# MCU.net
KiCad netlist of a schematic drawn in Altium Designer
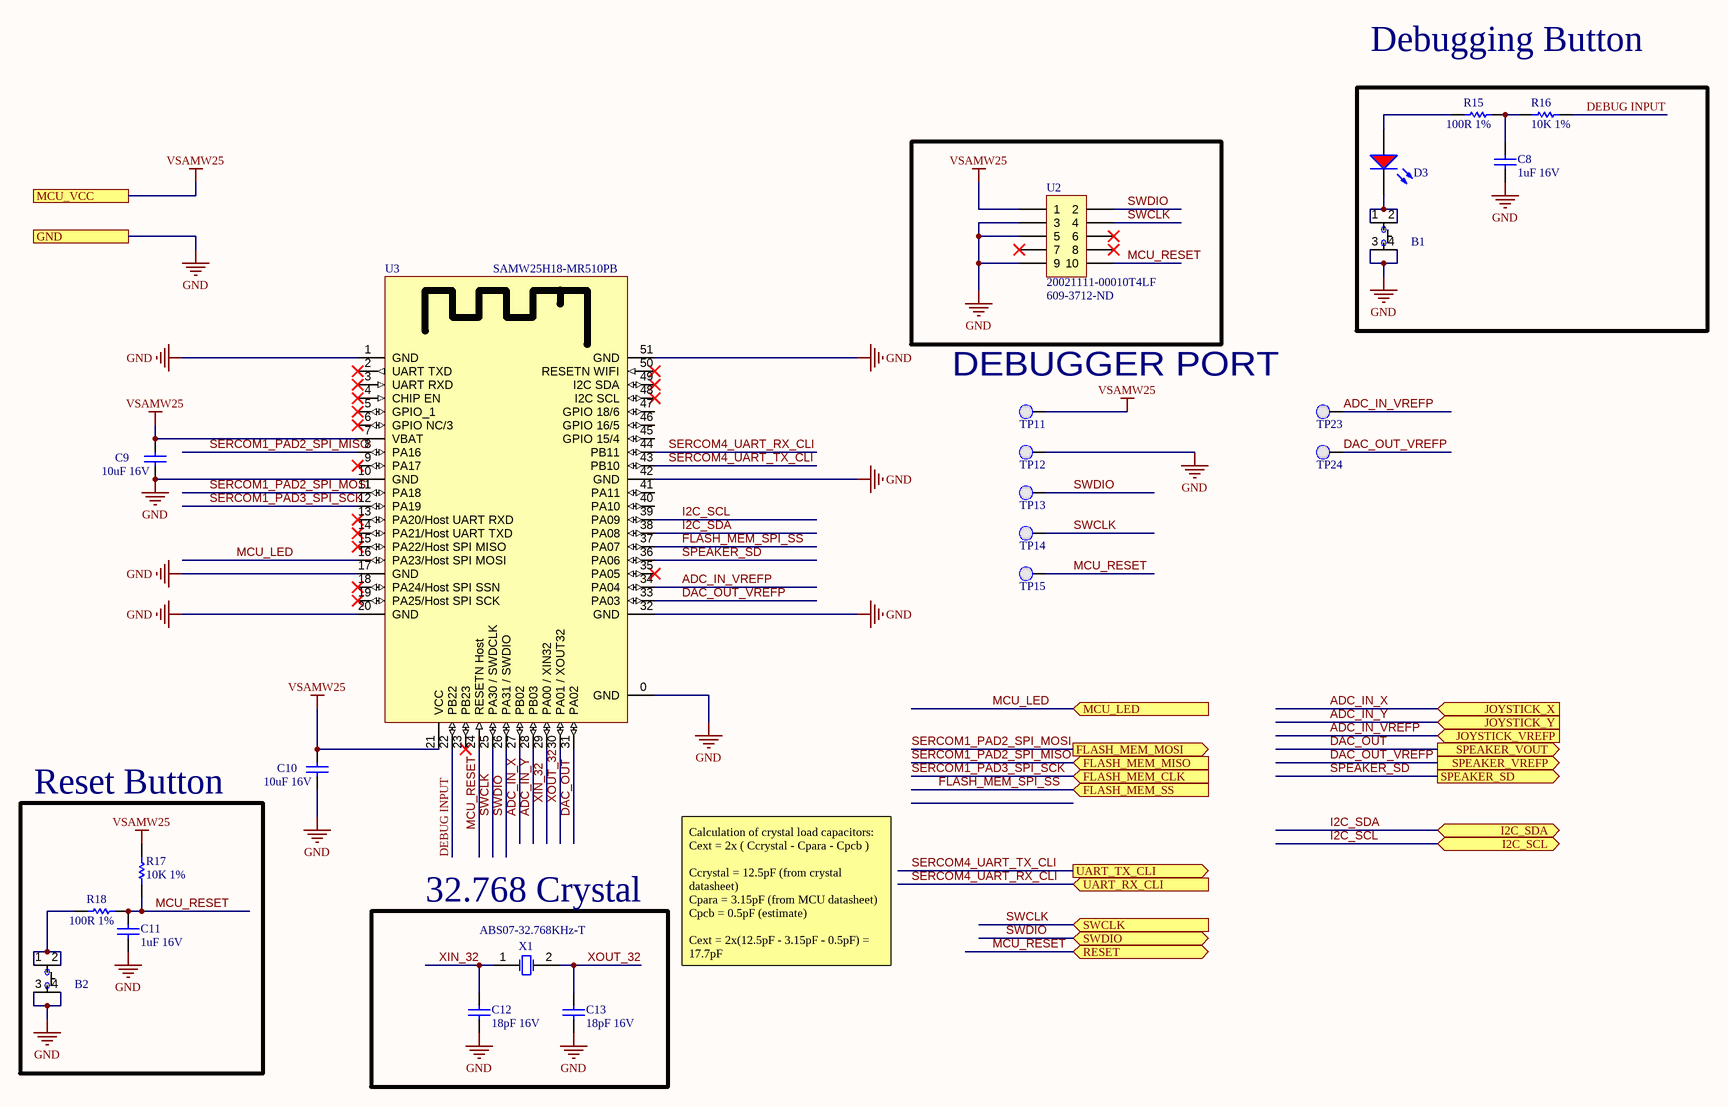
[diagram p0: MCU.SchDoc]

(export (version "E")
  (design (tool "Eeschema 10.0.6"))
  (components
    (comp (ref "B1")
      (value "PTS810 SJK 250 SMTR LFS")
      (footprint "PTS810 SJK 250 SMTR LFS")
      (description "SWITCH TACTILE SPST-NO 0.05A 16V Tactile Switch SPST-NO Top Actuated Surface Mount")
      (fields
        (field (name "MANUFACTURER") "ITT /  C&K Components")
        (field (name "MANUFACTURER PART NUMBER") "PTS810SJK250SMTRLFS")
      )
      (libsource (lib "Schematics") (part "PTS810 SJK 250 SMTR LFS"))
    )
    (comp (ref "B2")
      (value "PTS810 SJK 250 SMTR LFS")
      (footprint "PTS810 SJK 250 SMTR LFS")
      (description "SWITCH TACTILE SPST-NO 0.05A 16V Tactile Switch SPST-NO Top Actuated Surface Mount")
      (fields
        (field (name "MANUFACTURER") "ITT /  C&K Components")
        (field (name "MANUFACTURER PART NUMBER") "PTS810SJK250SMTRLFS")
      )
      (libsource (lib "Schematics") (part "PTS810 SJK 250 SMTR LFS"))
    )
    (comp (ref "C8")
      (value "1uF 16V")
      (footprint "CAPC0603(1608)100_N")
      (description "CAP 1uF 16V ±5% 0603 (1608 Metric) Thickness 1mm SMD")
      (fields (field (name "TOLERANCE") "Â±5%"))
      (libsource (lib "Altium Content Vault") (part "CAP"))
    )
    (comp (ref "C9")
      (value "10uF 16V")
      (footprint "CAPC0805(2012)145_L")
      (description "CAP 10uF 16V ±10% 0805 (2012 Metric) Thickness 1.45mm SMD")
      (fields (field (name "TOLERANCE") "Â±10%"))
      (libsource (lib "Altium Content Vault") (part "CAP"))
    )
    (comp (ref "C10")
      (value "10uF 16V")
      (footprint "CAPC0805(2012)145_L")
      (description "CAP 10uF 16V ±10% 0805 (2012 Metric) Thickness 1.45mm SMD")
      (fields (field (name "TOLERANCE") "Â±10%"))
      (libsource (lib "Altium Content Vault") (part "CAP"))
    )
    (comp (ref "C11")
      (value "1uF 16V")
      (footprint "CAPC0603(1608)100_N")
      (description "CAP 1uF 16V ±5% 0603 (1608 Metric) Thickness 1mm SMD")
      (fields (field (name "TOLERANCE") "Â±5%"))
      (libsource (lib "Altium Content Vault") (part "CAP"))
    )
    (comp (ref "C12")
      (value "18pF 16V")
      (footprint "CAPC0603(1608)100_N")
      (description "CAP 18pF 16V ±5% 0603 (1608 Metric) Thickness 1mm SMD")
      (fields (field (name "TOLERANCE") "Â±5%"))
      (libsource (lib "Altium Content Vault") (part "CAP"))
    )
    (comp (ref "C13")
      (value "18pF 16V")
      (footprint "CAPC0603(1608)100_N")
      (description "CAP 18pF 16V ±5% 0603 (1608 Metric) Thickness 1mm SMD")
      (fields (field (name "TOLERANCE") "Â±5%"))
      (libsource (lib "Altium Content Vault") (part "CAP"))
    )
    (comp (ref "D3")
      (value "LTST-C170CKT")
      (footprint "LTST-C170CKT_V")
      (description "LED Uni-Color Red, 100 mW, 200 mA, -55 to 85 degC, 2-Pin SMD, RoHS, Tape and Reel")
      (fields (field (name "MANUFACTURER") "Lite-On"))
      (libsource (lib "Altium Content Vault") (part "LED-RED-AK-2"))
    )
    (comp (ref "R15")
      (value "100R 1%")
      (footprint "RESC0603(1608)_N")
      (description "100R 0.1W 1% 0603 (1608 Metric)  SMD")
      (fields (field (name "TOLERANCE") "1 %") (field (name "POWER") "0.1 W"))
      (libsource (lib "Altium Content Vault") (part "RES"))
    )
    (comp (ref "R16")
      (value "10K 1%")
      (footprint "RESC0603(1608)_N")
      (description "10K 0.1W 1% 0603 (1608 Metric)  SMD")
      (fields (field (name "POWER") "0.1 W") (field (name "TOLERANCE") "1 %"))
      (libsource (lib "Altium Content Vault") (part "RES"))
    )
    (comp (ref "R17")
      (value "10K 1%")
      (footprint "RESC0603(1608)_N")
      (description "10K 0.1W 1% 0603 (1608 Metric)  SMD")
      (fields (field (name "POWER") "0.1 W") (field (name "TOLERANCE") "1 %"))
      (libsource (lib "Altium Content Vault") (part "RES"))
    )
    (comp (ref "R18")
      (value "100R 1%")
      (footprint "RESC0603(1608)_N")
      (description "100R 0.1W 1% 0603 (1608 Metric)  SMD")
      (fields (field (name "TOLERANCE") "1 %") (field (name "POWER") "0.1 W"))
      (libsource (lib "Altium Content Vault") (part "RES"))
    )
    (comp (ref "TP11")
      (value "0.1\" Pad")
      (footprint "PCBComponent")
      (libsource (lib "Components - 12.02.20 - 18.05") (part "0.1{dblquote} Pad-A.4"))
    )
    (comp (ref "TP12")
      (value "0.1\" Pad")
      (footprint "PCBComponent")
      (libsource (lib "Components - 12.02.20 - 18.05") (part "0.1{dblquote} Pad-A.4"))
    )
    (comp (ref "TP13")
      (value "0.1\" Pad")
      (footprint "PCBComponent")
      (libsource (lib "Components - 12.02.20 - 18.05") (part "0.1{dblquote} Pad-A.4"))
    )
    (comp (ref "TP14")
      (value "0.1\" Pad")
      (footprint "PCBComponent")
      (libsource (lib "Components - 12.02.20 - 18.05") (part "0.1{dblquote} Pad-A.4"))
    )
    (comp (ref "TP15")
      (value "0.1\" Pad")
      (footprint "PCBComponent")
      (libsource (lib "Components - 12.02.20 - 18.05") (part "0.1{dblquote} Pad-A.4"))
    )
    (comp (ref "TP23")
      (value "0.1\" Pad")
      (footprint "PCBComponent")
      (libsource (lib "Components - 12.02.20 - 18.05") (part "0.1{dblquote} Pad-A.4"))
    )
    (comp (ref "TP24")
      (value "0.1\" Pad")
      (footprint "PCBComponent")
      (libsource (lib "Components - 12.02.20 - 18.05") (part "0.1{dblquote} Pad-A.4"))
    )
    (comp (ref "U2")
      (value "20021111-00010T4LF")
      (footprint "20021111-00010T4LF")
      (description "CONN HEADER 10POS UNSHD VERT T/H")
      (fields
        (field (name "MANUFACTURER") "Amphenol / FCI")
        (field (name "SUPPLIER PART NUMBER 1") "609-3712-ND")
      )
      (libsource (lib "Schematics") (part "20021111-00010T4LF"))
    )
    (comp (ref "U3")
      (value "SAMW25H18-MR510PB")
      (footprint "SAMW25H18-MR510PB")
      (description "RF TXRX MODULE WIFI TRACE ANT")
      (fields
        (field (name "MANUFACTURER") "Atmel")
        (field (name "MANUFACTURER PART NUMBER") "ATSAMW25H18-MR510PB")
      )
      (libsource (lib "Schematics") (part "SAMW25H18-MR510PB"))
    )
    (comp (ref "X1")
      (value "ABS07-32.768KHz-T")
      (footprint "ABRA-ABS07-2_V")
      (description "Crystal, 32.768 kHz, 12.5 pF, -40 to 85 degC, SMD Low Profile 3.2 x 1.5 x 0.9 mm, Tape and Reel")
      (fields (field (name "MANUFACTURER") "Abracon"))
      (libsource (lib "Altium Content Vault") (part "ABRA-ABS07-2"))
    )
  )
  (nets
    (net (code "1") (name "/ADC_IN_VREFP") (class "Default")
      (node (ref "TP23") (pin "1") (pinfunction "PAD_1") (pintype "passive"))
      (node (ref "U3") (pin "34") (pinfunction "PA04_34") (pintype "bidirectional"))
    )
    (net (code "2") (name "/ADC_IN_X") (class "Default")
      (node (ref "U3") (pin "27") (pinfunction "PB02_27") (pintype "bidirectional"))
    )
    (net (code "3") (name "/ADC_IN_Y") (class "Default")
      (node (ref "U3") (pin "28") (pinfunction "PB03_28") (pintype "bidirectional"))
    )
    (net (code "4") (name "/DAC_OUT") (class "Default")
      (node (ref "U3") (pin "31") (pinfunction "PA02_31") (pintype "bidirectional"))
    )
    (net (code "5") (name "/DAC_OUT_VREFP") (class "Default")
      (node (ref "TP24") (pin "1") (pinfunction "PAD_1") (pintype "passive"))
      (node (ref "U3") (pin "33") (pinfunction "PA03_33") (pintype "bidirectional"))
    )
    (net (code "6") (name "/DEBUG INPUT") (class "Default")
      (node (ref "R16") (pin "1") (pinfunction "1_1") (pintype "passive"))
      (node (ref "U3") (pin "22") (pinfunction "PB22_22") (pintype "bidirectional"))
    )
    (net (code "7") (name "/FLASH_MEM_SPI_SS") (class "Default")
      (node (ref "U3") (pin "37") (pinfunction "PA07_37") (pintype "bidirectional"))
    )
    (net (code "8") (name "/I2C_SCL") (class "Default")
      (node (ref "U3") (pin "39") (pinfunction "PA09_39") (pintype "bidirectional"))
    )
    (net (code "9") (name "/I2C_SDA") (class "Default")
      (node (ref "U3") (pin "38") (pinfunction "PA08_38") (pintype "bidirectional"))
    )
    (net (code "10") (name "/MCU_LED") (class "Default")
      (node (ref "U3") (pin "16") (pinfunction "PA23/Host_SPI_MOSI_16") (pintype "bidirectional"))
    )
    (net (code "11") (name "/MCU_RESET") (class "Default")
      (node (ref "C11") (pin "2") (pinfunction "2_2") (pintype "passive"))
      (node (ref "R17") (pin "1") (pinfunction "1_1") (pintype "passive"))
      (node (ref "R18") (pin "2") (pinfunction "2_2") (pintype "passive"))
      (node (ref "TP15") (pin "1") (pinfunction "PAD_1") (pintype "passive"))
      (node (ref "U2") (pin "10") (pinfunction "10_10") (pintype "passive"))
      (node (ref "U3") (pin "24") (pinfunction "RESETN_Host_24") (pintype "input"))
    )
    (net (code "12") (name "/SERCOM1_PAD2_SPI_MISO") (class "Default")
      (node (ref "U3") (pin "8") (pinfunction "PA16_8") (pintype "bidirectional"))
    )
    (net (code "13") (name "/SERCOM1_PAD2_SPI_MOSI") (class "Default")
      (node (ref "U3") (pin "11") (pinfunction "PA18_11") (pintype "bidirectional"))
    )
    (net (code "14") (name "/SERCOM1_PAD3_SPI_SCK") (class "Default")
      (node (ref "U3") (pin "12") (pinfunction "PA19_12") (pintype "bidirectional"))
    )
    (net (code "15") (name "/SERCOM4_UART_RX_CLI") (class "Default")
      (node (ref "U3") (pin "44") (pinfunction "PB11_44") (pintype "bidirectional"))
    )
    (net (code "16") (name "/SERCOM4_UART_TX_CLI") (class "Default")
      (node (ref "U3") (pin "43") (pinfunction "PB10_43") (pintype "bidirectional"))
    )
    (net (code "17") (name "/SPEAKER_SD") (class "Default")
      (node (ref "U3") (pin "36") (pinfunction "PA06_36") (pintype "bidirectional"))
    )
    (net (code "18") (name "/SWCLK") (class "Default")
      (node (ref "TP14") (pin "1") (pinfunction "PAD_1") (pintype "passive"))
      (node (ref "U2") (pin "4") (pinfunction "4_4") (pintype "passive"))
      (node (ref "U3") (pin "25") (pinfunction "PA30_/_SWDCLK_25") (pintype "bidirectional"))
    )
    (net (code "19") (name "/SWDIO") (class "Default")
      (node (ref "TP13") (pin "1") (pinfunction "PAD_1") (pintype "passive"))
      (node (ref "U2") (pin "2") (pinfunction "2_2") (pintype "passive"))
      (node (ref "U3") (pin "26") (pinfunction "PA31_/_SWDIO_26") (pintype "bidirectional"))
    )
    (net (code "20") (name "/XIN_32") (class "Default")
      (node (ref "C12") (pin "2") (pinfunction "2_2") (pintype "passive"))
      (node (ref "U3") (pin "29") (pinfunction "PA00_/_XIN32_29") (pintype "bidirectional"))
      (node (ref "X1") (pin "1") (pinfunction "X1_1") (pintype "passive"))
    )
    (net (code "21") (name "/XOUT_32") (class "Default")
      (node (ref "C13") (pin "2") (pinfunction "2_2") (pintype "passive"))
      (node (ref "U3") (pin "30") (pinfunction "PA01_/_XOUT32_30") (pintype "bidirectional"))
      (node (ref "X1") (pin "2") (pinfunction "X2_2") (pintype "passive"))
    )
    (net (code "22") (name "GND") (class "Default")
      (node (ref "B1") (pin "3") (pinfunction "3_3") (pintype "power_in"))
      (node (ref "B1") (pin "4") (pinfunction "4_4") (pintype "power_in"))
      (node (ref "B2") (pin "3") (pinfunction "3_3") (pintype "power_in"))
      (node (ref "B2") (pin "4") (pinfunction "4_4") (pintype "power_in"))
      (node (ref "C10") (pin "1") (pinfunction "1_1") (pintype "passive"))
      (node (ref "C11") (pin "1") (pinfunction "1_1") (pintype "passive"))
      (node (ref "C12") (pin "1") (pinfunction "1_1") (pintype "passive"))
      (node (ref "C13") (pin "1") (pinfunction "1_1") (pintype "passive"))
      (node (ref "C8") (pin "1") (pinfunction "1_1") (pintype "passive"))
      (node (ref "C9") (pin "1") (pinfunction "1_1") (pintype "passive"))
      (node (ref "TP12") (pin "1") (pinfunction "PAD_1") (pintype "passive"))
      (node (ref "U2") (pin "3") (pinfunction "3_3") (pintype "passive"))
      (node (ref "U2") (pin "5") (pinfunction "5_5") (pintype "passive"))
      (node (ref "U2") (pin "9") (pinfunction "9_9") (pintype "passive"))
      (node (ref "U3") (pin "0") (pinfunction "GND_0") (pintype "power_in"))
      (node (ref "U3") (pin "1") (pinfunction "GND_1") (pintype "power_in"))
      (node (ref "U3") (pin "10") (pinfunction "GND_10") (pintype "power_in"))
      (node (ref "U3") (pin "17") (pinfunction "GND_17") (pintype "power_in"))
      (node (ref "U3") (pin "20") (pinfunction "GND_20") (pintype "power_in"))
      (node (ref "U3") (pin "32") (pinfunction "GND_32") (pintype "power_in"))
      (node (ref "U3") (pin "42") (pinfunction "GND_42") (pintype "power_in"))
      (node (ref "U3") (pin "51") (pinfunction "GND_51") (pintype "power_in"))
    )
    (net (code "23") (name "Net-(B2-Pad1)") (class "Default")
      (node (ref "B2") (pin "1") (pinfunction "1_1") (pintype "power_in"))
      (node (ref "B2") (pin "2") (pinfunction "2_2") (pintype "power_in"))
      (node (ref "R18") (pin "1") (pinfunction "1_1") (pintype "passive"))
    )
    (net (code "24") (name "Net-(C8-Pad2)") (class "Default")
      (node (ref "C8") (pin "2") (pinfunction "2_2") (pintype "passive"))
      (node (ref "R15") (pin "2") (pinfunction "2_2") (pintype "passive"))
      (node (ref "R16") (pin "2") (pinfunction "2_2") (pintype "passive"))
    )
    (net (code "25") (name "Net-(D3-A)") (class "Default")
      (node (ref "D3") (pin "1") (pinfunction "A_1") (pintype "passive"))
      (node (ref "R15") (pin "1") (pinfunction "1_1") (pintype "passive"))
    )
    (net (code "26") (name "Net-(D3-K)") (class "Default")
      (node (ref "B1") (pin "1") (pinfunction "1_1") (pintype "power_in"))
      (node (ref "B1") (pin "2") (pinfunction "2_2") (pintype "power_in"))
      (node (ref "D3") (pin "2") (pinfunction "K_2") (pintype "passive"))
    )
    (net (code "27") (name "VSAMW25") (class "Default")
      (node (ref "C10") (pin "2") (pinfunction "2_2") (pintype "passive"))
      (node (ref "C9") (pin "2") (pinfunction "2_2") (pintype "passive"))
      (node (ref "R17") (pin "2") (pinfunction "2_2") (pintype "passive"))
      (node (ref "TP11") (pin "1") (pinfunction "PAD_1") (pintype "passive"))
      (node (ref "U2") (pin "1") (pinfunction "1_1") (pintype "passive"))
      (node (ref "U3") (pin "21") (pinfunction "VCC_21") (pintype "power_in"))
      (node (ref "U3") (pin "7") (pinfunction "VBAT_7") (pintype "power_in"))
    )
    (net (code "28") (name "unconnected-(U2-Pad6)") (class "Default")
      (node (ref "U2") (pin "6") (pinfunction "6_6") (pintype "passive+no_connect"))
    )
    (net (code "29") (name "unconnected-(U2-Pad7)") (class "Default")
      (node (ref "U2") (pin "7") (pinfunction "7_7") (pintype "passive+no_connect"))
    )
    (net (code "30") (name "unconnected-(U2-Pad8)") (class "Default")
      (node (ref "U2") (pin "8") (pinfunction "8_8") (pintype "passive+no_connect"))
    )
    (net (code "31") (name "unconnected-(U3-CHIP_EN-Pad4)") (class "Default")
      (node (ref "U3") (pin "4") (pinfunction "CHIP_EN_4") (pintype "input+no_connect"))
    )
    (net (code "32") (name "unconnected-(U3-GPIO_1-Pad5)") (class "Default")
      (node (ref "U3") (pin "5") (pinfunction "GPIO_1_5") (pintype "bidirectional+no_connect"))
    )
    (net (code "33") (name "unconnected-(U3-GPIO_15{slash}4-Pad45)") (class "Default")
      (node (ref "U3") (pin "45") (pinfunction "GPIO_15/4_45") (pintype "bidirectional"))
    )
    (net (code "34") (name "unconnected-(U3-GPIO_16{slash}5-Pad46)") (class "Default")
      (node (ref "U3") (pin "46") (pinfunction "GPIO_16/5_46") (pintype "bidirectional"))
    )
    (net (code "35") (name "unconnected-(U3-GPIO_18{slash}6-Pad47)") (class "Default")
      (node (ref "U3") (pin "47") (pinfunction "GPIO_18/6_47") (pintype "bidirectional"))
    )
    (net (code "36") (name "unconnected-(U3-GPIO_NC{slash}3-Pad6)") (class "Default")
      (node (ref "U3") (pin "6") (pinfunction "GPIO_NC/3_6") (pintype "bidirectional+no_connect"))
    )
    (net (code "37") (name "unconnected-(U3-I2C_SCL-Pad48)") (class "Default")
      (node (ref "U3") (pin "48") (pinfunction "I2C_SCL_48") (pintype "bidirectional+no_connect"))
    )
    (net (code "38") (name "unconnected-(U3-I2C_SDA-Pad49)") (class "Default")
      (node (ref "U3") (pin "49") (pinfunction "I2C_SDA_49") (pintype "bidirectional+no_connect"))
    )
    (net (code "39") (name "unconnected-(U3-PA05-Pad35)") (class "Default")
      (node (ref "U3") (pin "35") (pinfunction "PA05_35") (pintype "bidirectional+no_connect"))
    )
    (net (code "40") (name "unconnected-(U3-PA10-Pad40)") (class "Default")
      (node (ref "U3") (pin "40") (pinfunction "PA10_40") (pintype "bidirectional"))
    )
    (net (code "41") (name "unconnected-(U3-PA11-Pad41)") (class "Default")
      (node (ref "U3") (pin "41") (pinfunction "PA11_41") (pintype "bidirectional"))
    )
    (net (code "42") (name "unconnected-(U3-PA17-Pad9)") (class "Default")
      (node (ref "U3") (pin "9") (pinfunction "PA17_9") (pintype "bidirectional+no_connect"))
    )
    (net (code "43") (name "unconnected-(U3-PA20{slash}Host_UART_RXD-Pad13)") (class "Default")
      (node (ref "U3") (pin "13") (pinfunction "PA20/Host_UART_RXD_13") (pintype "bidirectional+no_connect"))
    )
    (net (code "44") (name "unconnected-(U3-PA21{slash}Host_UART_TXD-Pad14)") (class "Default")
      (node (ref "U3") (pin "14") (pinfunction "PA21/Host_UART_TXD_14") (pintype "bidirectional+no_connect"))
    )
    (net (code "45") (name "unconnected-(U3-PA22{slash}Host_SPI_MISO-Pad15)") (class "Default")
      (node (ref "U3") (pin "15") (pinfunction "PA22/Host_SPI_MISO_15") (pintype "bidirectional+no_connect"))
    )
    (net (code "46") (name "unconnected-(U3-PA24{slash}Host_SPI_SSN-Pad18)") (class "Default")
      (node (ref "U3") (pin "18") (pinfunction "PA24/Host_SPI_SSN_18") (pintype "bidirectional+no_connect"))
    )
    (net (code "47") (name "unconnected-(U3-PA25{slash}Host_SPI_SCK-Pad19)") (class "Default")
      (node (ref "U3") (pin "19") (pinfunction "PA25/Host_SPI_SCK_19") (pintype "bidirectional+no_connect"))
    )
    (net (code "48") (name "unconnected-(U3-PB23-Pad23)") (class "Default")
      (node (ref "U3") (pin "23") (pinfunction "PB23_23") (pintype "bidirectional+no_connect"))
    )
    (net (code "49") (name "unconnected-(U3-RESETN_WIFI-Pad50)") (class "Default")
      (node (ref "U3") (pin "50") (pinfunction "RESETN_WIFI_50") (pintype "input+no_connect"))
    )
    (net (code "50") (name "unconnected-(U3-UART_RXD-Pad3)") (class "Default")
      (node (ref "U3") (pin "3") (pinfunction "UART_RXD_3") (pintype "input+no_connect"))
    )
    (net (code "51") (name "unconnected-(U3-UART_TXD-Pad2)") (class "Default")
      (node (ref "U3") (pin "2") (pinfunction "UART_TXD_2") (pintype "output+no_connect"))
    )
  )
)
